# Decawave.net
KiCad netlist of a schematic drawn in Altium Designer
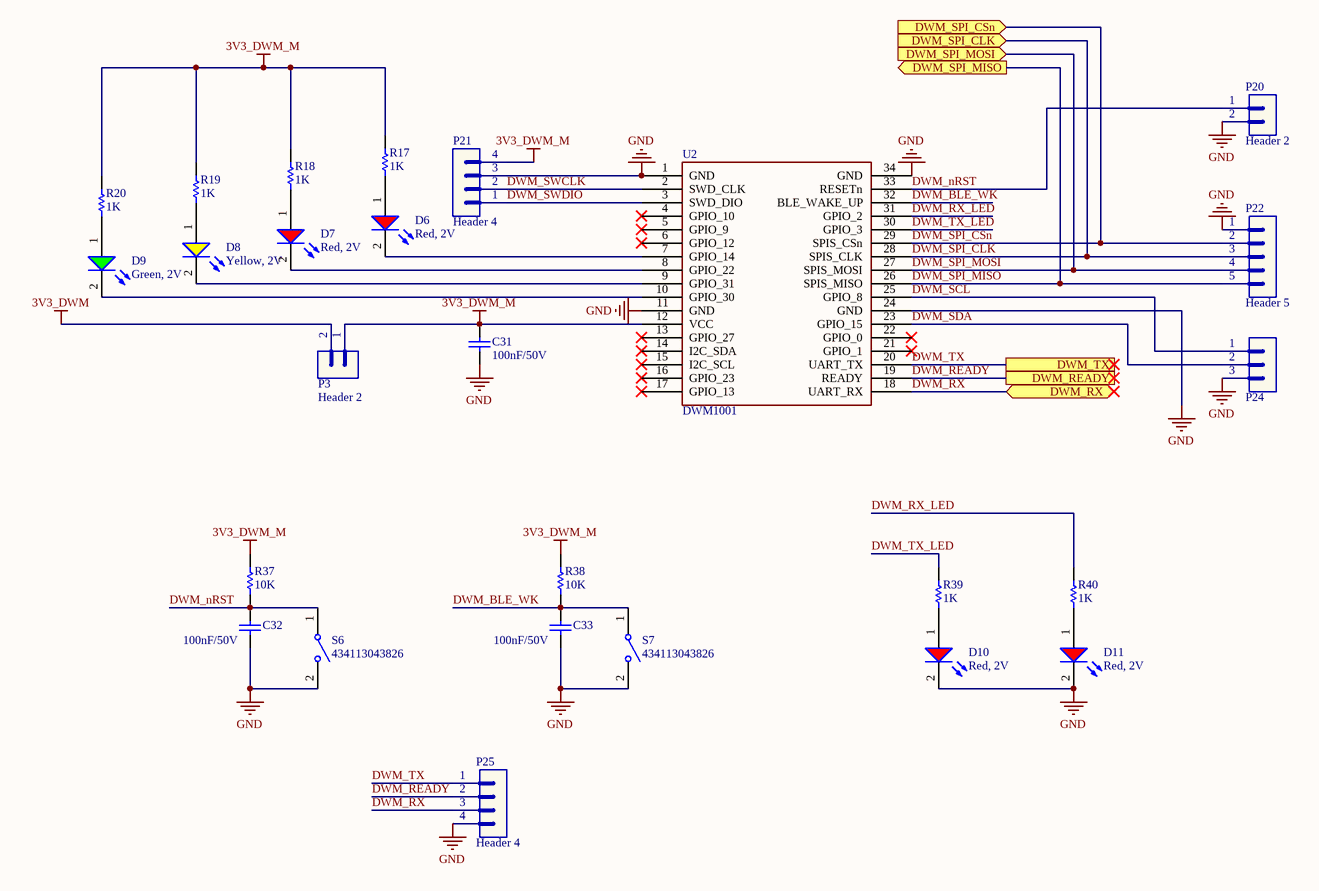
[diagram p0: Decawave.schdoc]

(export (version "E")
  (design (tool "Eeschema 10.0.6"))
  (components
    (comp (ref "C31")
      (value "100nF/50V")
      (footprint "CAP-SM-0805")
      (description "CAP CER 0.1UF 50V Y5V 0805")
      (fields
        (field (name "MANUFACTURER") "Samsung Electro-Mechanics")
        (field (name "MANUFACTURER PART NUMBER") "CL21F104ZBCNNNC")
      )
      (libsource (lib "Capacitor") (part "Cap-100nF-50V-0805"))
    )
    (comp (ref "C32")
      (value "100nF/50V")
      (footprint "CAP-SM-0805")
      (description "CAP CER 0.1UF 50V Y5V 0805")
      (fields
        (field (name "MANUFACTURER") "Samsung Electro-Mechanics")
        (field (name "MANUFACTURER PART NUMBER") "CL21F104ZBCNNNC")
      )
      (libsource (lib "Capacitor") (part "Cap-100nF-50V-0805"))
    )
    (comp (ref "C33")
      (value "100nF/50V")
      (footprint "CAP-SM-0805")
      (description "CAP CER 0.1UF 50V Y5V 0805")
      (fields
        (field (name "MANUFACTURER") "Samsung Electro-Mechanics")
        (field (name "MANUFACTURER PART NUMBER") "CL21F104ZBCNNNC")
      )
      (libsource (lib "Capacitor") (part "Cap-100nF-50V-0805"))
    )
    (comp (ref "D6")
      (value "Red, 2V")
      (footprint "LED_0805_Blue")
      (description "LED RED CLEAR T-1 T/H")
      (fields
        (field (name "MANUFACTURER") "Kingbright")
        (field (name "MANUFACTURER PART NUMBER") "WP710A10SEC/J3")
      )
      (libsource (lib "LED") (part "LED-RED-TH-3mm"))
    )
    (comp (ref "D7")
      (value "Red, 2V")
      (footprint "LED_0805_Blue")
      (description "LED RED CLEAR T-1 T/H")
      (fields
        (field (name "MANUFACTURER") "Kingbright")
        (field (name "MANUFACTURER PART NUMBER") "WP710A10SEC/J3")
      )
      (libsource (lib "LED") (part "LED-RED-TH-3mm"))
    )
    (comp (ref "D8")
      (value "Yellow, 2V")
      (footprint "LED_0805_Blue")
      (fields (field (name "Comment") "LED-YELLOW-TH-3mm"))
      (libsource (lib "LED") (part "LED-YELLOW-TH-3mm"))
    )
    (comp (ref "D9")
      (value "Green, 2V")
      (footprint "LED_0805_Blue")
      (description "LED GREEN CLEAR T-1 T/H")
      (fields
        (field (name "MANUFACTURER") "Kingbright")
        (field (name "MANUFACTURER PART NUMBER") "WP710A10ZGC/G")
      )
      (libsource (lib "LED") (part "LED-GREEN-TH-3mm"))
    )
    (comp (ref "D10")
      (value "Red, 2V")
      (footprint "LED_0805_Blue")
      (description "LED RED CLEAR T-1 T/H")
      (fields
        (field (name "MANUFACTURER") "Kingbright")
        (field (name "MANUFACTURER PART NUMBER") "WP710A10SEC/J3")
      )
      (libsource (lib "LED") (part "LED-RED-TH-3mm"))
    )
    (comp (ref "D11")
      (value "Red, 2V")
      (footprint "LED_0805_Blue")
      (description "LED RED CLEAR T-1 T/H")
      (fields
        (field (name "MANUFACTURER") "Kingbright")
        (field (name "MANUFACTURER PART NUMBER") "WP710A10SEC/J3")
      )
      (libsource (lib "LED") (part "LED-RED-TH-3mm"))
    )
    (comp (ref "P3")
      (value "Header 2")
      (footprint "JP2")
      (description "Header, 2-Pin")
      (fields (field (name "PUBLISHER") "Altium Limited"))
      (libsource (lib "Header-connector") (part "Header 2"))
    )
    (comp (ref "P20")
      (value "Header 2")
      (footprint "JP2")
      (description "Header, 2-Pin")
      (fields (field (name "PUBLISHER") "Altium Limited"))
      (libsource (lib "") (part "Header 2_1"))
    )
    (comp (ref "P21")
      (value "Header 4")
      (footprint "JP4")
      (description "Header, 4-Pin")
      (fields (field (name "PUBLISHER") "Altium Limited"))
      (libsource (lib "") (part "Header 4_1"))
    )
    (comp (ref "P22")
      (value "Header 5")
      (footprint "JP5")
      (description "Header, 5-Pin")
      (fields (field (name "PUBLISHER") "Altium Limited"))
      (libsource (lib "Header-connector") (part "Header 5"))
    )
    (comp (ref "P24")
      (value "Header 3")
      (footprint "JP3")
      (description "Header, 3-Pin")
      (fields (field (name "PUBLISHER") "Altium Limited"))
      (libsource (lib "Header-connector") (part "Header 3"))
    )
    (comp (ref "P25")
      (value "Header 4")
      (footprint "JP4")
      (description "Header, 4-Pin")
      (fields (field (name "PUBLISHER") "Altium Limited"))
      (libsource (lib "Header-connector") (part "Header 4"))
    )
    (comp (ref "R17")
      (value "1K")
      (footprint "RES-SM-0805")
      (description "RES 1K OHM 1% 1/4W 0805")
      (fields
        (field (name "MANUFACTURER") "Stackpole Electronics Inc")
        (field (name "MANUFACTURER PART NUMBER") "RNCP0805FTD1K00")
      )
      (libsource (lib "Resistor") (part "Res-1K-0805"))
    )
    (comp (ref "R18")
      (value "1K")
      (footprint "RES-SM-0805")
      (description "RES 1K OHM 1% 1/4W 0805")
      (fields
        (field (name "MANUFACTURER") "Stackpole Electronics Inc")
        (field (name "MANUFACTURER PART NUMBER") "RNCP0805FTD1K00")
      )
      (libsource (lib "Resistor") (part "Res-1K-0805"))
    )
    (comp (ref "R19")
      (value "1K")
      (footprint "RES-SM-0805")
      (description "RES 1K OHM 1% 1/4W 0805")
      (fields
        (field (name "MANUFACTURER") "Stackpole Electronics Inc")
        (field (name "MANUFACTURER PART NUMBER") "RNCP0805FTD1K00")
      )
      (libsource (lib "Resistor") (part "Res-1K-0805"))
    )
    (comp (ref "R20")
      (value "1K")
      (footprint "RES-SM-0805")
      (description "RES 1K OHM 1% 1/4W 0805")
      (fields
        (field (name "MANUFACTURER") "Stackpole Electronics Inc")
        (field (name "MANUFACTURER PART NUMBER") "RNCP0805FTD1K00")
      )
      (libsource (lib "Resistor") (part "Res-1K-0805"))
    )
    (comp (ref "R37")
      (value "10K")
      (footprint "Resistor:RES-SM-0805")
      (description "RES 10K OHM 1% 1/4W 0805")
      (fields
        (field (name "MANUFACTURER") "Stackpole Electronics Inc")
        (field (name "MANUFACTURER PART NUMBER") "RNCP0805FTD10K0")
      )
      (libsource (lib "Resistor") (part "Res-10k-0805"))
    )
    (comp (ref "R38")
      (value "10K")
      (footprint "Resistor:RES-SM-0805")
      (description "RES 10K OHM 1% 1/4W 0805")
      (fields
        (field (name "MANUFACTURER") "Stackpole Electronics Inc")
        (field (name "MANUFACTURER PART NUMBER") "RNCP0805FTD10K0")
      )
      (libsource (lib "Resistor") (part "Res-10k-0805"))
    )
    (comp (ref "R39")
      (value "1K")
      (footprint "Resistor:RES-SM-0805")
      (description "RES 1K OHM 1% 1/4W 0805")
      (fields
        (field (name "MANUFACTURER") "Stackpole Electronics Inc")
        (field (name "MANUFACTURER PART NUMBER") "RNCP0805FTD1K00")
      )
      (libsource (lib "Resistor") (part "Res-1K-0805"))
    )
    (comp (ref "R40")
      (value "1K")
      (footprint "Resistor:RES-SM-0805")
      (description "RES 1K OHM 1% 1/4W 0805")
      (fields
        (field (name "MANUFACTURER") "Stackpole Electronics Inc")
        (field (name "MANUFACTURER PART NUMBER") "RNCP0805FTD1K00")
      )
      (libsource (lib "Resistor") (part "Res-1K-0805"))
    )
    (comp (ref "S6")
      (value "434113043826")
      (footprint "434113043826")
      (description "WS-TASV J-Bend SMT Tact Switch 6x3.5mm, height 4.3mm, 260gf")
      (fields (field (name "PUBLISHER") "Wurth Elektronik"))
      (libsource (lib "434113043826_Altium_WS-TASV_rev20a") (part "434113043826"))
    )
    (comp (ref "S7")
      (value "434113043826")
      (footprint "434113043826")
      (description "WS-TASV J-Bend SMT Tact Switch 6x3.5mm, height 4.3mm, 260gf")
      (fields (field (name "PUBLISHER") "Wurth Elektronik"))
      (libsource (lib "434113043826_Altium_WS-TASV_rev20a") (part "434113043826"))
    )
    (comp (ref "U2") (value "DWM1001") (footprint "DWM1001") (libsource (lib "PIF_robot") (part "DWM1001")))
  )
  (nets
    (net (code "1") (name "/DWM_BLE_WK") (class "Default")
      (node (ref "C33") (pin "1") (pinfunction "1_1") (pintype "passive"))
      (node (ref "R38") (pin "1") (pinfunction "1_1") (pintype "passive"))
      (node (ref "S7") (pin "1") (pinfunction "1_1") (pintype "passive"))
      (node (ref "U2") (pin "32") (pinfunction "BLE_WAKE_UP_32") (pintype "passive"))
    )
    (net (code "2") (name "/DWM_READY") (class "Default")
      (node (ref "P25") (pin "2") (pinfunction "2_2") (pintype "passive"))
      (node (ref "U2") (pin "19") (pinfunction "READY_19") (pintype "passive"))
    )
    (net (code "3") (name "/DWM_RX") (class "Default")
      (node (ref "P25") (pin "3") (pinfunction "3_3") (pintype "passive"))
      (node (ref "U2") (pin "18") (pinfunction "UART_RX_18") (pintype "passive"))
    )
    (net (code "4") (name "/DWM_RX_LED") (class "Default")
      (node (ref "R40") (pin "2") (pinfunction "2_2") (pintype "passive"))
      (node (ref "U2") (pin "31") (pinfunction "GPIO_2_31") (pintype "passive"))
    )
    (net (code "5") (name "/DWM_SCL") (class "Default")
      (node (ref "P24") (pin "1") (pinfunction "1_1") (pintype "passive"))
      (node (ref "U2") (pin "25") (pinfunction "GPIO_8_25") (pintype "passive"))
    )
    (net (code "6") (name "/DWM_SDA") (class "Default")
      (node (ref "P24") (pin "2") (pinfunction "2_2") (pintype "passive"))
      (node (ref "U2") (pin "23") (pinfunction "GPIO_15_23") (pintype "passive"))
    )
    (net (code "7") (name "/DWM_SPI_CLK") (class "Default")
      (node (ref "P22") (pin "3") (pinfunction "3_3") (pintype "passive"))
      (node (ref "U2") (pin "28") (pinfunction "SPIS_CLK_28") (pintype "passive"))
    )
    (net (code "8") (name "/DWM_SPI_CSn") (class "Default")
      (node (ref "P22") (pin "2") (pinfunction "2_2") (pintype "passive"))
      (node (ref "U2") (pin "29") (pinfunction "SPIS_CSn_29") (pintype "passive"))
    )
    (net (code "9") (name "/DWM_SPI_MISO") (class "Default")
      (node (ref "P22") (pin "5") (pinfunction "5_5") (pintype "passive"))
      (node (ref "U2") (pin "26") (pinfunction "SPIS_MISO_26") (pintype "passive"))
    )
    (net (code "10") (name "/DWM_SPI_MOSI") (class "Default")
      (node (ref "P22") (pin "4") (pinfunction "4_4") (pintype "passive"))
      (node (ref "U2") (pin "27") (pinfunction "SPIS_MOSI_27") (pintype "passive"))
    )
    (net (code "11") (name "/DWM_SWCLK") (class "Default")
      (node (ref "P21") (pin "2") (pinfunction "2_2") (pintype "passive"))
      (node (ref "U2") (pin "2") (pinfunction "SWD_CLK_2") (pintype "passive"))
    )
    (net (code "12") (name "/DWM_SWDIO") (class "Default")
      (node (ref "P21") (pin "1") (pinfunction "1_1") (pintype "passive"))
      (node (ref "U2") (pin "3") (pinfunction "SWD_DIO_3") (pintype "passive"))
    )
    (net (code "13") (name "/DWM_TX") (class "Default")
      (node (ref "P25") (pin "1") (pinfunction "1_1") (pintype "passive"))
      (node (ref "U2") (pin "20") (pinfunction "UART_TX_20") (pintype "passive"))
    )
    (net (code "14") (name "/DWM_TX_LED") (class "Default")
      (node (ref "R39") (pin "2") (pinfunction "2_2") (pintype "passive"))
      (node (ref "U2") (pin "30") (pinfunction "GPIO_3_30") (pintype "passive"))
    )
    (net (code "15") (name "/DWM_nRST") (class "Default")
      (node (ref "C32") (pin "1") (pinfunction "1_1") (pintype "passive"))
      (node (ref "P20") (pin "1") (pinfunction "1_1") (pintype "passive"))
      (node (ref "R37") (pin "1") (pinfunction "1_1") (pintype "passive"))
      (node (ref "S6") (pin "1") (pinfunction "1_1") (pintype "passive"))
      (node (ref "U2") (pin "33") (pinfunction "RESETn_33") (pintype "passive"))
    )
    (net (code "16") (name "3V3_DWM") (class "Default")
      (node (ref "P3") (pin "2") (pinfunction "2_2") (pintype "passive"))
    )
    (net (code "17") (name "3V3_DWM_M") (class "Default")
      (node (ref "C31") (pin "2") (pinfunction "2_2") (pintype "passive"))
      (node (ref "P21") (pin "4") (pinfunction "4_4") (pintype "passive"))
      (node (ref "P3") (pin "1") (pinfunction "1_1") (pintype "passive"))
      (node (ref "R17") (pin "2") (pinfunction "2_2") (pintype "passive"))
      (node (ref "R18") (pin "2") (pinfunction "2_2") (pintype "passive"))
      (node (ref "R19") (pin "2") (pinfunction "2_2") (pintype "passive"))
      (node (ref "R20") (pin "2") (pinfunction "2_2") (pintype "passive"))
      (node (ref "R37") (pin "2") (pinfunction "2_2") (pintype "passive"))
      (node (ref "R38") (pin "2") (pinfunction "2_2") (pintype "passive"))
      (node (ref "U2") (pin "12") (pinfunction "VCC_12") (pintype "passive"))
    )
    (net (code "18") (name "GND") (class "Default")
      (node (ref "C31") (pin "1") (pinfunction "1_1") (pintype "passive"))
      (node (ref "C32") (pin "2") (pinfunction "2_2") (pintype "passive"))
      (node (ref "C33") (pin "2") (pinfunction "2_2") (pintype "passive"))
      (node (ref "D10") (pin "2") (pinfunction "K_2") (pintype "passive"))
      (node (ref "D11") (pin "2") (pinfunction "K_2") (pintype "passive"))
      (node (ref "P20") (pin "2") (pinfunction "2_2") (pintype "passive"))
      (node (ref "P21") (pin "3") (pinfunction "3_3") (pintype "passive"))
      (node (ref "P22") (pin "1") (pinfunction "1_1") (pintype "passive"))
      (node (ref "P24") (pin "3") (pinfunction "3_3") (pintype "passive"))
      (node (ref "P25") (pin "4") (pinfunction "4_4") (pintype "passive"))
      (node (ref "S6") (pin "2") (pinfunction "2_2") (pintype "passive"))
      (node (ref "S7") (pin "2") (pinfunction "2_2") (pintype "passive"))
      (node (ref "U2") (pin "1") (pinfunction "GND_1") (pintype "passive"))
      (node (ref "U2") (pin "11") (pinfunction "GND_11") (pintype "passive"))
      (node (ref "U2") (pin "24") (pinfunction "GND_24") (pintype "passive"))
      (node (ref "U2") (pin "34") (pinfunction "GND_34") (pintype "passive"))
    )
    (net (code "19") (name "Net-(D6-A)") (class "Default")
      (node (ref "D6") (pin "1") (pinfunction "A_1") (pintype "passive"))
      (node (ref "R17") (pin "1") (pinfunction "1_1") (pintype "passive"))
    )
    (net (code "20") (name "Net-(D6-K)") (class "Default")
      (node (ref "D6") (pin "2") (pinfunction "K_2") (pintype "passive"))
      (node (ref "U2") (pin "7") (pinfunction "GPIO_14_7") (pintype "passive"))
    )
    (net (code "21") (name "Net-(D7-A)") (class "Default")
      (node (ref "D7") (pin "1") (pinfunction "A_1") (pintype "passive"))
      (node (ref "R18") (pin "1") (pinfunction "1_1") (pintype "passive"))
    )
    (net (code "22") (name "Net-(D7-K)") (class "Default")
      (node (ref "D7") (pin "2") (pinfunction "K_2") (pintype "passive"))
      (node (ref "U2") (pin "8") (pinfunction "GPIO_22_8") (pintype "passive"))
    )
    (net (code "23") (name "Net-(D8-A)") (class "Default")
      (node (ref "D8") (pin "1") (pinfunction "A_1") (pintype "passive"))
      (node (ref "R19") (pin "1") (pinfunction "1_1") (pintype "passive"))
    )
    (net (code "24") (name "Net-(D8-K)") (class "Default")
      (node (ref "D8") (pin "2") (pinfunction "K_2") (pintype "passive"))
      (node (ref "U2") (pin "9") (pinfunction "GPIO_31_9") (pintype "passive"))
    )
    (net (code "25") (name "Net-(D9-A)") (class "Default")
      (node (ref "D9") (pin "1") (pinfunction "A_1") (pintype "passive"))
      (node (ref "R20") (pin "1") (pinfunction "1_1") (pintype "passive"))
    )
    (net (code "26") (name "Net-(D9-K)") (class "Default")
      (node (ref "D9") (pin "2") (pinfunction "K_2") (pintype "passive"))
      (node (ref "U2") (pin "10") (pinfunction "GPIO_30_10") (pintype "passive"))
    )
    (net (code "27") (name "Net-(D10-A)") (class "Default")
      (node (ref "D10") (pin "1") (pinfunction "A_1") (pintype "passive"))
      (node (ref "R39") (pin "1") (pinfunction "1_1") (pintype "passive"))
    )
    (net (code "28") (name "Net-(D11-A)") (class "Default")
      (node (ref "D11") (pin "1") (pinfunction "A_1") (pintype "passive"))
      (node (ref "R40") (pin "1") (pinfunction "1_1") (pintype "passive"))
    )
    (net (code "29") (name "unconnected-(U2-GPIO_0-Pad22)") (class "Default")
      (node (ref "U2") (pin "22") (pinfunction "GPIO_0_22") (pintype "passive+no_connect"))
    )
    (net (code "30") (name "unconnected-(U2-GPIO_1-Pad21)") (class "Default")
      (node (ref "U2") (pin "21") (pinfunction "GPIO_1_21") (pintype "passive+no_connect"))
    )
    (net (code "31") (name "unconnected-(U2-GPIO_9-Pad5)") (class "Default")
      (node (ref "U2") (pin "5") (pinfunction "GPIO_9_5") (pintype "passive+no_connect"))
    )
    (net (code "32") (name "unconnected-(U2-GPIO_10-Pad4)") (class "Default")
      (node (ref "U2") (pin "4") (pinfunction "GPIO_10_4") (pintype "passive+no_connect"))
    )
    (net (code "33") (name "unconnected-(U2-GPIO_12-Pad6)") (class "Default")
      (node (ref "U2") (pin "6") (pinfunction "GPIO_12_6") (pintype "passive+no_connect"))
    )
    (net (code "34") (name "unconnected-(U2-GPIO_13-Pad17)") (class "Default")
      (node (ref "U2") (pin "17") (pinfunction "GPIO_13_17") (pintype "passive+no_connect"))
    )
    (net (code "35") (name "unconnected-(U2-GPIO_23-Pad16)") (class "Default")
      (node (ref "U2") (pin "16") (pinfunction "GPIO_23_16") (pintype "passive+no_connect"))
    )
    (net (code "36") (name "unconnected-(U2-GPIO_27-Pad13)") (class "Default")
      (node (ref "U2") (pin "13") (pinfunction "GPIO_27_13") (pintype "passive+no_connect"))
    )
    (net (code "37") (name "unconnected-(U2-I2C_SCL-Pad15)") (class "Default")
      (node (ref "U2") (pin "15") (pinfunction "I2C_SCL_15") (pintype "passive+no_connect"))
    )
    (net (code "38") (name "unconnected-(U2-I2C_SDA-Pad14)") (class "Default")
      (node (ref "U2") (pin "14") (pinfunction "I2C_SDA_14") (pintype "passive+no_connect"))
    )
  )
)
